# Comparadores.net
KiCad netlist of a schematic drawn in EAGLE
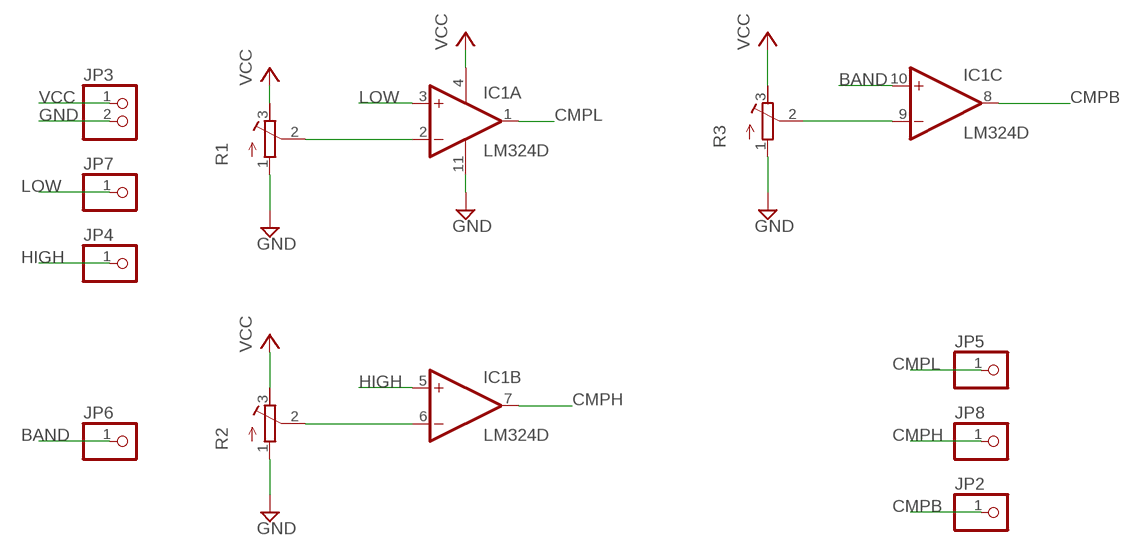
[diagram p0: schematic, sheet 1]

(export (version "E")
  (design (tool "Eeschema 10.0.6"))
  (components
    (comp (ref "IC1")
      (value "LM324D")
      (footprint "eagle-import:SO14")
      (libsource (lib "eagle-import") (part "LM324D"))
    )
    (comp (ref "JP2")
      (value "PINHD-1X1")
      (footprint "eagle-import:1X01")
      (libsource (lib "eagle-import") (part "PINHD-1X1"))
    )
    (comp (ref "JP3")
      (value "PINHD-1X2")
      (footprint "eagle-import:1X02")
      (libsource (lib "eagle-import") (part "PINHD-1X2"))
    )
    (comp (ref "JP4")
      (value "PINHD-1X1")
      (footprint "eagle-import:1X01")
      (libsource (lib "eagle-import") (part "PINHD-1X1"))
    )
    (comp (ref "JP5")
      (value "PINHD-1X1")
      (footprint "eagle-import:1X01")
      (libsource (lib "eagle-import") (part "PINHD-1X1"))
    )
    (comp (ref "JP6")
      (value "PINHD-1X1")
      (footprint "eagle-import:1X01")
      (libsource (lib "eagle-import") (part "PINHD-1X1"))
    )
    (comp (ref "JP7")
      (value "PINHD-1X1")
      (footprint "eagle-import:1X01")
      (libsource (lib "eagle-import") (part "PINHD-1X1"))
    )
    (comp (ref "JP8")
      (value "PINHD-1X1")
      (footprint "eagle-import:1X01")
      (libsource (lib "eagle-import") (part "PINHD-1X1"))
    )
    (comp (ref "R1")
      (value "R-TRIMM64W")
      (footprint "eagle-import:RTRIM64W")
      (libsource (lib "eagle-import") (part "R-TRIMM64W"))
    )
    (comp (ref "R2")
      (value "R-TRIMM64W")
      (footprint "eagle-import:RTRIM64W")
      (libsource (lib "eagle-import") (part "R-TRIMM64W"))
    )
    (comp (ref "R3")
      (value "R-TRIMM64W")
      (footprint "eagle-import:RTRIM64W")
      (libsource (lib "eagle-import") (part "R-TRIMM64W"))
    )
  )
  (nets
    (net (code "1") (name "/BAND") (class "Default")
      (node (ref "IC1") (pin "10") (pinfunction "+IN_10") (pintype "input"))
      (node (ref "JP6") (pin "1") (pinfunction "1_1") (pintype "passive"))
    )
    (net (code "2") (name "/CMPB") (class "Default")
      (node (ref "IC1") (pin "8") (pinfunction "OUT_8") (pintype "output"))
      (node (ref "JP2") (pin "1") (pinfunction "1_1") (pintype "passive"))
    )
    (net (code "3") (name "/CMPH") (class "Default")
      (node (ref "IC1") (pin "7") (pinfunction "OUT_7") (pintype "output"))
      (node (ref "JP8") (pin "1") (pinfunction "1_1") (pintype "passive"))
    )
    (net (code "4") (name "/CMPL") (class "Default")
      (node (ref "IC1") (pin "1") (pinfunction "OUT_1") (pintype "output"))
      (node (ref "JP5") (pin "1") (pinfunction "1_1") (pintype "passive"))
    )
    (net (code "5") (name "/HIGH") (class "Default")
      (node (ref "IC1") (pin "5") (pinfunction "+IN_5") (pintype "input"))
      (node (ref "JP4") (pin "1") (pinfunction "1_1") (pintype "passive"))
    )
    (net (code "6") (name "/LOW") (class "Default")
      (node (ref "IC1") (pin "3") (pinfunction "+IN_3") (pintype "input"))
      (node (ref "JP7") (pin "1") (pinfunction "1_1") (pintype "passive"))
    )
    (net (code "7") (name "GND") (class "Default")
      (node (ref "IC1") (pin "11") (pinfunction "V-_11") (pintype "power_in"))
      (node (ref "JP3") (pin "2") (pinfunction "2_2") (pintype "passive"))
      (node (ref "R1") (pin "1") (pinfunction "A_1") (pintype "passive"))
      (node (ref "R2") (pin "1") (pinfunction "A_1") (pintype "passive"))
      (node (ref "R3") (pin "1") (pinfunction "A_1") (pintype "passive"))
    )
    (net (code "8") (name "Net-(IC1A--IN)") (class "Default")
      (node (ref "IC1") (pin "2") (pinfunction "-IN_2") (pintype "input"))
      (node (ref "R1") (pin "2") (pinfunction "S_2") (pintype "passive"))
    )
    (net (code "9") (name "Net-(IC1B--IN)") (class "Default")
      (node (ref "IC1") (pin "6") (pinfunction "-IN_6") (pintype "input"))
      (node (ref "R2") (pin "2") (pinfunction "S_2") (pintype "passive"))
    )
    (net (code "10") (name "Net-(IC1C--IN)") (class "Default")
      (node (ref "IC1") (pin "9") (pinfunction "-IN_9") (pintype "input"))
      (node (ref "R3") (pin "2") (pinfunction "S_2") (pintype "passive"))
    )
    (net (code "11") (name "VCC") (class "Default")
      (node (ref "IC1") (pin "4") (pinfunction "V+_4") (pintype "power_in"))
      (node (ref "JP3") (pin "1") (pinfunction "1_1") (pintype "passive"))
      (node (ref "R1") (pin "3") (pinfunction "E_3") (pintype "passive"))
      (node (ref "R2") (pin "3") (pinfunction "E_3") (pintype "passive"))
      (node (ref "R3") (pin "3") (pinfunction "E_3") (pintype "passive"))
    )
  )
)
